# 1-Schematic_No_filter_booth_pcb.net
KiCad netlist of a schematic drawn in EasyEDA
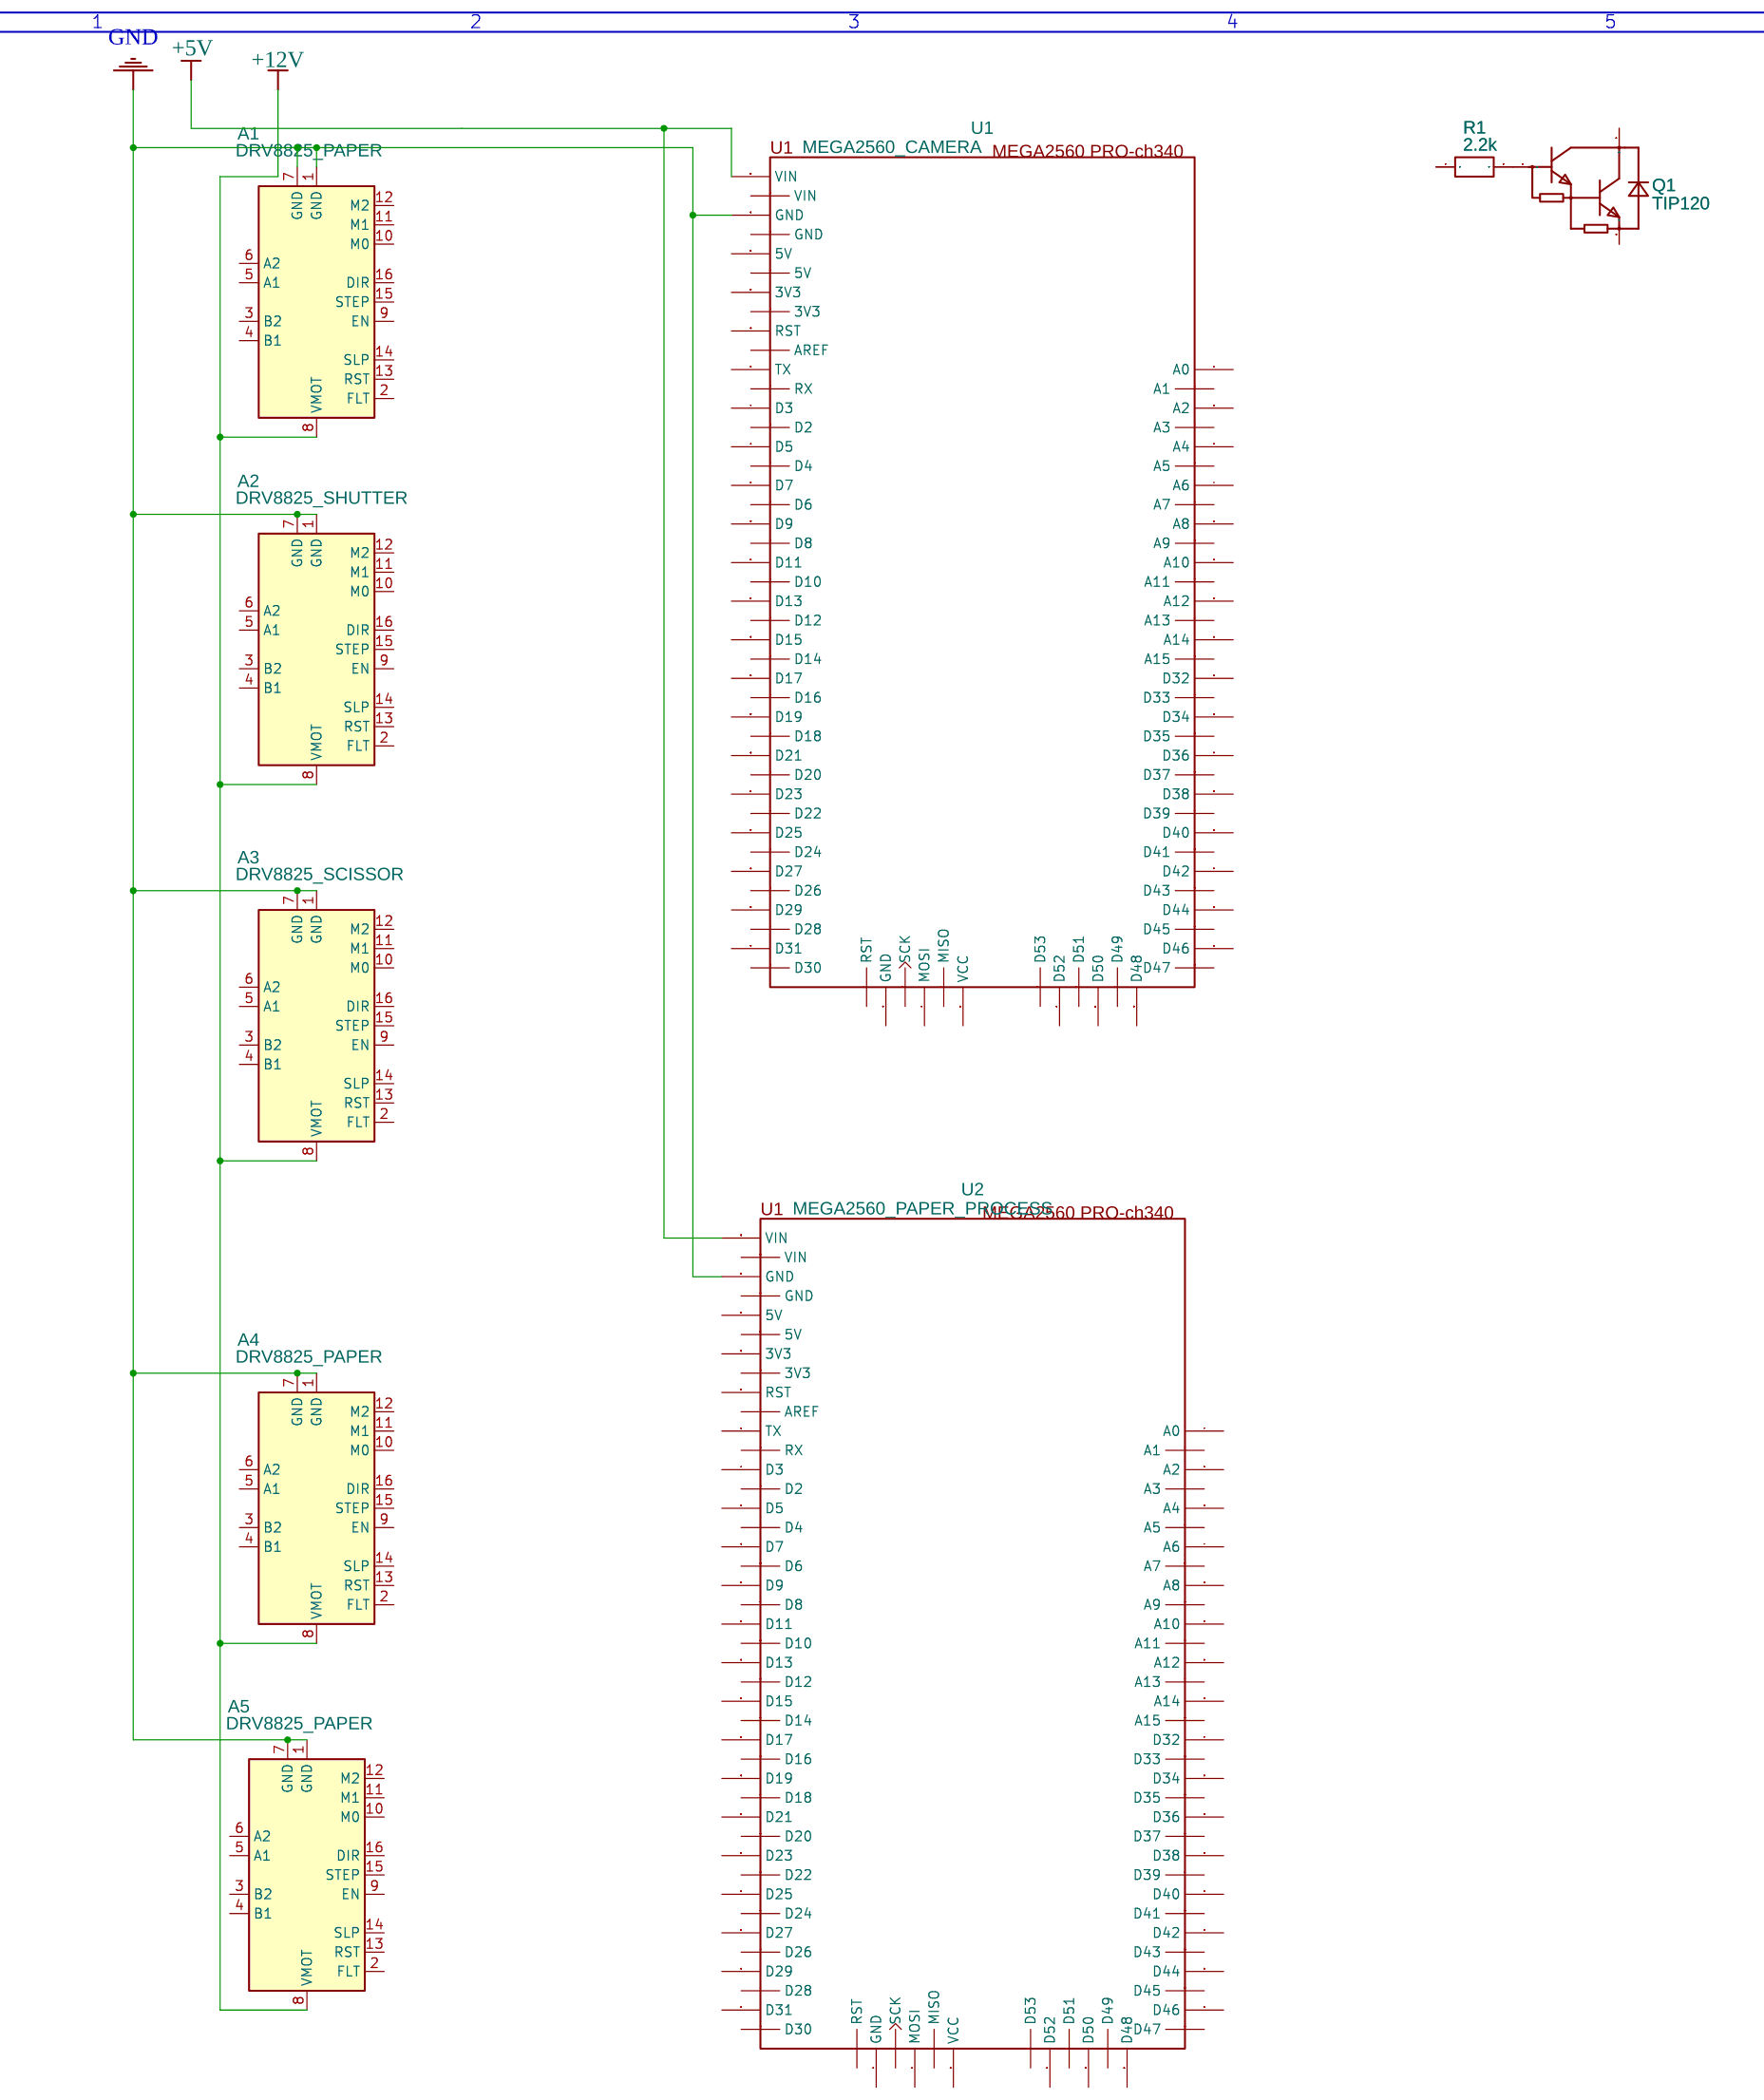
[diagram p0: schematic sheet]

(export (version "E")
  (design (tool "Eeschema 10.0.6"))
  (components
    (comp (ref "A1") (value "DRV8825_PAPER") (libsource (lib "") (part "Pololu_Breakout_DRV8825")))
    (comp (ref "A2") (value "DRV8825_SHUTTER") (libsource (lib "") (part "Pololu_Breakout_DRV8825")))
    (comp (ref "A3") (value "DRV8825_SCISSOR") (libsource (lib "") (part "Pololu_Breakout_DRV8825")))
    (comp (ref "A4") (value "DRV8825_PAPER") (libsource (lib "") (part "Pololu_Breakout_DRV8825")))
    (comp (ref "A5") (value "DRV8825_PAPER") (libsource (lib "") (part "Pololu_Breakout_DRV8825")))
    (comp (ref "Q1")
      (value "TIP120")
      (fields (field (name "BOM_Supplier Part") "C262990"))
      (libsource (lib "") (part "TIP120"))
    )
    (comp (ref "R1") (value "2.2k") (libsource (lib "") (part "Res_1210(1/3W)_EU")))
    (comp (ref "U1")
      (value "MEGA2560_CAMERA")
      (fields (field (name "BOM_Manufacturer Part") "MEGA2560 PRO-ch340G"))
      (libsource (lib "") (part "MEGA2560 PRO-ch340G"))
    )
    (comp (ref "U2")
      (value "MEGA2560_PAPER_PROCESS")
      (fields (field (name "BOM_Manufacturer Part") "MEGA2560 PRO-ch340G"))
      (libsource (lib "") (part "MEGA2560 PRO-ch340G"))
    )
  )
  (nets
    (net (code "1") (name "+5V") (class "Default")
      (node (ref "U1") (pin "86") (pinfunction "VIN_86") (pintype "unspecified"))
      (node (ref "U2") (pin "86") (pinfunction "VIN_86") (pintype "unspecified"))
    )
    (net (code "2") (name "+12V") (class "Default")
      (node (ref "A1") (pin "8") (pinfunction "VMOT_8") (pintype "bidirectional"))
      (node (ref "A2") (pin "8") (pinfunction "VMOT_8") (pintype "bidirectional"))
      (node (ref "A3") (pin "8") (pinfunction "VMOT_8") (pintype "bidirectional"))
      (node (ref "A4") (pin "8") (pinfunction "VMOT_8") (pintype "bidirectional"))
      (node (ref "A5") (pin "8") (pinfunction "VMOT_8") (pintype "bidirectional"))
    )
    (net (code "3") (name "GND") (class "Default")
      (node (ref "A1") (pin "1") (pinfunction "GND_1") (pintype "bidirectional"))
      (node (ref "A1") (pin "7") (pinfunction "GND_7") (pintype "bidirectional"))
      (node (ref "A2") (pin "1") (pinfunction "GND_1") (pintype "bidirectional"))
      (node (ref "A2") (pin "7") (pinfunction "GND_7") (pintype "bidirectional"))
      (node (ref "A3") (pin "1") (pinfunction "GND_1") (pintype "bidirectional"))
      (node (ref "A3") (pin "7") (pinfunction "GND_7") (pintype "bidirectional"))
      (node (ref "A4") (pin "1") (pinfunction "GND_1") (pintype "bidirectional"))
      (node (ref "A4") (pin "7") (pinfunction "GND_7") (pintype "bidirectional"))
      (node (ref "A5") (pin "1") (pinfunction "GND_1") (pintype "bidirectional"))
      (node (ref "A5") (pin "7") (pinfunction "GND_7") (pintype "bidirectional"))
      (node (ref "U1") (pin "84") (pinfunction "GND_84") (pintype "unspecified"))
      (node (ref "U2") (pin "84") (pinfunction "GND_84") (pintype "unspecified"))
    )
    (net (code "4") (name "Net-(Q1-B)") (class "Default")
      (node (ref "Q1") (pin "1") (pinfunction "B_1") (pintype "input"))
      (node (ref "R1") (pin "2") (pinfunction "2_2") (pintype "unspecified"))
    )
    (net (code "5") (name "unconnected-(A1-A1-Pad5)") (class "Default")
      (node (ref "A1") (pin "5") (pinfunction "A1_5") (pintype "output"))
    )
    (net (code "6") (name "unconnected-(A1-A2-Pad6)") (class "Default")
      (node (ref "A1") (pin "6") (pinfunction "A2_6") (pintype "output"))
    )
    (net (code "7") (name "unconnected-(A1-B1-Pad4)") (class "Default")
      (node (ref "A1") (pin "4") (pinfunction "B1_4") (pintype "output"))
    )
    (net (code "8") (name "unconnected-(A1-B2-Pad3)") (class "Default")
      (node (ref "A1") (pin "3") (pinfunction "B2_3") (pintype "output"))
    )
    (net (code "9") (name "unconnected-(A1-DIR-Pad16)") (class "Default")
      (node (ref "A1") (pin "16") (pinfunction "DIR_16") (pintype "input"))
    )
    (net (code "10") (name "unconnected-(A1-EN-Pad9)") (class "Default")
      (node (ref "A1") (pin "9") (pinfunction "EN_9") (pintype "input"))
    )
    (net (code "11") (name "unconnected-(A1-FLT-Pad2)") (class "Default")
      (node (ref "A1") (pin "2") (pinfunction "FLT_2") (pintype "output"))
    )
    (net (code "12") (name "unconnected-(A1-M0-Pad10)") (class "Default")
      (node (ref "A1") (pin "10") (pinfunction "M0_10") (pintype "input"))
    )
    (net (code "13") (name "unconnected-(A1-M1-Pad11)") (class "Default")
      (node (ref "A1") (pin "11") (pinfunction "M1_11") (pintype "input"))
    )
    (net (code "14") (name "unconnected-(A1-M2-Pad12)") (class "Default")
      (node (ref "A1") (pin "12") (pinfunction "M2_12") (pintype "input"))
    )
    (net (code "15") (name "unconnected-(A1-RST-Pad13)") (class "Default")
      (node (ref "A1") (pin "13") (pinfunction "RST_13") (pintype "input"))
    )
    (net (code "16") (name "unconnected-(A1-SLP-Pad14)") (class "Default")
      (node (ref "A1") (pin "14") (pinfunction "SLP_14") (pintype "input"))
    )
    (net (code "17") (name "unconnected-(A1-STEP-Pad15)") (class "Default")
      (node (ref "A1") (pin "15") (pinfunction "STEP_15") (pintype "input"))
    )
    (net (code "18") (name "unconnected-(A2-A1-Pad5)") (class "Default")
      (node (ref "A2") (pin "5") (pinfunction "A1_5") (pintype "output"))
    )
    (net (code "19") (name "unconnected-(A2-A2-Pad6)") (class "Default")
      (node (ref "A2") (pin "6") (pinfunction "A2_6") (pintype "output"))
    )
    (net (code "20") (name "unconnected-(A2-B1-Pad4)") (class "Default")
      (node (ref "A2") (pin "4") (pinfunction "B1_4") (pintype "output"))
    )
    (net (code "21") (name "unconnected-(A2-B2-Pad3)") (class "Default")
      (node (ref "A2") (pin "3") (pinfunction "B2_3") (pintype "output"))
    )
    (net (code "22") (name "unconnected-(A2-DIR-Pad16)") (class "Default")
      (node (ref "A2") (pin "16") (pinfunction "DIR_16") (pintype "input"))
    )
    (net (code "23") (name "unconnected-(A2-EN-Pad9)") (class "Default")
      (node (ref "A2") (pin "9") (pinfunction "EN_9") (pintype "input"))
    )
    (net (code "24") (name "unconnected-(A2-FLT-Pad2)") (class "Default")
      (node (ref "A2") (pin "2") (pinfunction "FLT_2") (pintype "output"))
    )
    (net (code "25") (name "unconnected-(A2-M0-Pad10)") (class "Default")
      (node (ref "A2") (pin "10") (pinfunction "M0_10") (pintype "input"))
    )
    (net (code "26") (name "unconnected-(A2-M1-Pad11)") (class "Default")
      (node (ref "A2") (pin "11") (pinfunction "M1_11") (pintype "input"))
    )
    (net (code "27") (name "unconnected-(A2-M2-Pad12)") (class "Default")
      (node (ref "A2") (pin "12") (pinfunction "M2_12") (pintype "input"))
    )
    (net (code "28") (name "unconnected-(A2-RST-Pad13)") (class "Default")
      (node (ref "A2") (pin "13") (pinfunction "RST_13") (pintype "input"))
    )
    (net (code "29") (name "unconnected-(A2-SLP-Pad14)") (class "Default")
      (node (ref "A2") (pin "14") (pinfunction "SLP_14") (pintype "input"))
    )
    (net (code "30") (name "unconnected-(A2-STEP-Pad15)") (class "Default")
      (node (ref "A2") (pin "15") (pinfunction "STEP_15") (pintype "input"))
    )
    (net (code "31") (name "unconnected-(A3-A1-Pad5)") (class "Default")
      (node (ref "A3") (pin "5") (pinfunction "A1_5") (pintype "output"))
    )
    (net (code "32") (name "unconnected-(A3-A2-Pad6)") (class "Default")
      (node (ref "A3") (pin "6") (pinfunction "A2_6") (pintype "output"))
    )
    (net (code "33") (name "unconnected-(A3-B1-Pad4)") (class "Default")
      (node (ref "A3") (pin "4") (pinfunction "B1_4") (pintype "output"))
    )
    (net (code "34") (name "unconnected-(A3-B2-Pad3)") (class "Default")
      (node (ref "A3") (pin "3") (pinfunction "B2_3") (pintype "output"))
    )
    (net (code "35") (name "unconnected-(A3-DIR-Pad16)") (class "Default")
      (node (ref "A3") (pin "16") (pinfunction "DIR_16") (pintype "input"))
    )
    (net (code "36") (name "unconnected-(A3-EN-Pad9)") (class "Default")
      (node (ref "A3") (pin "9") (pinfunction "EN_9") (pintype "input"))
    )
    (net (code "37") (name "unconnected-(A3-FLT-Pad2)") (class "Default")
      (node (ref "A3") (pin "2") (pinfunction "FLT_2") (pintype "output"))
    )
    (net (code "38") (name "unconnected-(A3-M0-Pad10)") (class "Default")
      (node (ref "A3") (pin "10") (pinfunction "M0_10") (pintype "input"))
    )
    (net (code "39") (name "unconnected-(A3-M1-Pad11)") (class "Default")
      (node (ref "A3") (pin "11") (pinfunction "M1_11") (pintype "input"))
    )
    (net (code "40") (name "unconnected-(A3-M2-Pad12)") (class "Default")
      (node (ref "A3") (pin "12") (pinfunction "M2_12") (pintype "input"))
    )
    (net (code "41") (name "unconnected-(A3-RST-Pad13)") (class "Default")
      (node (ref "A3") (pin "13") (pinfunction "RST_13") (pintype "input"))
    )
    (net (code "42") (name "unconnected-(A3-SLP-Pad14)") (class "Default")
      (node (ref "A3") (pin "14") (pinfunction "SLP_14") (pintype "input"))
    )
    (net (code "43") (name "unconnected-(A3-STEP-Pad15)") (class "Default")
      (node (ref "A3") (pin "15") (pinfunction "STEP_15") (pintype "input"))
    )
    (net (code "44") (name "unconnected-(A4-A1-Pad5)") (class "Default")
      (node (ref "A4") (pin "5") (pinfunction "A1_5") (pintype "output"))
    )
    (net (code "45") (name "unconnected-(A4-A2-Pad6)") (class "Default")
      (node (ref "A4") (pin "6") (pinfunction "A2_6") (pintype "output"))
    )
    (net (code "46") (name "unconnected-(A4-B1-Pad4)") (class "Default")
      (node (ref "A4") (pin "4") (pinfunction "B1_4") (pintype "output"))
    )
    (net (code "47") (name "unconnected-(A4-B2-Pad3)") (class "Default")
      (node (ref "A4") (pin "3") (pinfunction "B2_3") (pintype "output"))
    )
    (net (code "48") (name "unconnected-(A4-DIR-Pad16)") (class "Default")
      (node (ref "A4") (pin "16") (pinfunction "DIR_16") (pintype "input"))
    )
    (net (code "49") (name "unconnected-(A4-EN-Pad9)") (class "Default")
      (node (ref "A4") (pin "9") (pinfunction "EN_9") (pintype "input"))
    )
    (net (code "50") (name "unconnected-(A4-FLT-Pad2)") (class "Default")
      (node (ref "A4") (pin "2") (pinfunction "FLT_2") (pintype "output"))
    )
    (net (code "51") (name "unconnected-(A4-M0-Pad10)") (class "Default")
      (node (ref "A4") (pin "10") (pinfunction "M0_10") (pintype "input"))
    )
    (net (code "52") (name "unconnected-(A4-M1-Pad11)") (class "Default")
      (node (ref "A4") (pin "11") (pinfunction "M1_11") (pintype "input"))
    )
    (net (code "53") (name "unconnected-(A4-M2-Pad12)") (class "Default")
      (node (ref "A4") (pin "12") (pinfunction "M2_12") (pintype "input"))
    )
    (net (code "54") (name "unconnected-(A4-RST-Pad13)") (class "Default")
      (node (ref "A4") (pin "13") (pinfunction "RST_13") (pintype "input"))
    )
    (net (code "55") (name "unconnected-(A4-SLP-Pad14)") (class "Default")
      (node (ref "A4") (pin "14") (pinfunction "SLP_14") (pintype "input"))
    )
    (net (code "56") (name "unconnected-(A4-STEP-Pad15)") (class "Default")
      (node (ref "A4") (pin "15") (pinfunction "STEP_15") (pintype "input"))
    )
    (net (code "57") (name "unconnected-(A5-A1-Pad5)") (class "Default")
      (node (ref "A5") (pin "5") (pinfunction "A1_5") (pintype "output"))
    )
    (net (code "58") (name "unconnected-(A5-A2-Pad6)") (class "Default")
      (node (ref "A5") (pin "6") (pinfunction "A2_6") (pintype "output"))
    )
    (net (code "59") (name "unconnected-(A5-B1-Pad4)") (class "Default")
      (node (ref "A5") (pin "4") (pinfunction "B1_4") (pintype "output"))
    )
    (net (code "60") (name "unconnected-(A5-B2-Pad3)") (class "Default")
      (node (ref "A5") (pin "3") (pinfunction "B2_3") (pintype "output"))
    )
    (net (code "61") (name "unconnected-(A5-DIR-Pad16)") (class "Default")
      (node (ref "A5") (pin "16") (pinfunction "DIR_16") (pintype "input"))
    )
    (net (code "62") (name "unconnected-(A5-EN-Pad9)") (class "Default")
      (node (ref "A5") (pin "9") (pinfunction "EN_9") (pintype "input"))
    )
    (net (code "63") (name "unconnected-(A5-FLT-Pad2)") (class "Default")
      (node (ref "A5") (pin "2") (pinfunction "FLT_2") (pintype "output"))
    )
    (net (code "64") (name "unconnected-(A5-M0-Pad10)") (class "Default")
      (node (ref "A5") (pin "10") (pinfunction "M0_10") (pintype "input"))
    )
    (net (code "65") (name "unconnected-(A5-M1-Pad11)") (class "Default")
      (node (ref "A5") (pin "11") (pinfunction "M1_11") (pintype "input"))
    )
    (net (code "66") (name "unconnected-(A5-M2-Pad12)") (class "Default")
      (node (ref "A5") (pin "12") (pinfunction "M2_12") (pintype "input"))
    )
    (net (code "67") (name "unconnected-(A5-RST-Pad13)") (class "Default")
      (node (ref "A5") (pin "13") (pinfunction "RST_13") (pintype "input"))
    )
    (net (code "68") (name "unconnected-(A5-SLP-Pad14)") (class "Default")
      (node (ref "A5") (pin "14") (pinfunction "SLP_14") (pintype "input"))
    )
    (net (code "69") (name "unconnected-(A5-STEP-Pad15)") (class "Default")
      (node (ref "A5") (pin "15") (pinfunction "STEP_15") (pintype "input"))
    )
    (net (code "70") (name "unconnected-(Q1-C-Pad2)") (class "Default")
      (node (ref "Q1") (pin "2") (pinfunction "C_2") (pintype "input"))
    )
    (net (code "71") (name "unconnected-(Q1-E-Pad3)") (class "Default")
      (node (ref "Q1") (pin "3") (pinfunction "E_3") (pintype "input"))
    )
    (net (code "72") (name "unconnected-(R1-Pad1)") (class "Default")
      (node (ref "R1") (pin "1") (pinfunction "1_1") (pintype "unspecified"))
    )
    (net (code "73") (name "unconnected-(U1-3V3-Pad79)") (class "Default")
      (node (ref "U1") (pin "79") (pinfunction "3V3_79") (pintype "unspecified"))
    )
    (net (code "74") (name "unconnected-(U1-3V3-Pad80)") (class "Default")
      (node (ref "U1") (pin "80") (pinfunction "3V3_80") (pintype "unspecified"))
    )
    (net (code "75") (name "unconnected-(U1-5V-Pad81)") (class "Default")
      (node (ref "U1") (pin "81") (pinfunction "5V_81") (pintype "unspecified"))
    )
    (net (code "76") (name "unconnected-(U1-5V-Pad82)") (class "Default")
      (node (ref "U1") (pin "82") (pinfunction "5V_82") (pintype "unspecified"))
    )
    (net (code "77") (name "unconnected-(U1-A0-Pad1)") (class "Default")
      (node (ref "U1") (pin "1") (pinfunction "A0_1") (pintype "unspecified"))
    )
    (net (code "78") (name "unconnected-(U1-A1-Pad2)") (class "Default")
      (node (ref "U1") (pin "2") (pinfunction "A1_2") (pintype "unspecified"))
    )
    (net (code "79") (name "unconnected-(U1-A2-Pad3)") (class "Default")
      (node (ref "U1") (pin "3") (pinfunction "A2_3") (pintype "unspecified"))
    )
    (net (code "80") (name "unconnected-(U1-A3-Pad4)") (class "Default")
      (node (ref "U1") (pin "4") (pinfunction "A3_4") (pintype "unspecified"))
    )
    (net (code "81") (name "unconnected-(U1-A4-Pad5)") (class "Default")
      (node (ref "U1") (pin "5") (pinfunction "A4_5") (pintype "unspecified"))
    )
    (net (code "82") (name "unconnected-(U1-A5-Pad6)") (class "Default")
      (node (ref "U1") (pin "6") (pinfunction "A5_6") (pintype "unspecified"))
    )
    (net (code "83") (name "unconnected-(U1-A6-Pad7)") (class "Default")
      (node (ref "U1") (pin "7") (pinfunction "A6_7") (pintype "unspecified"))
    )
    (net (code "84") (name "unconnected-(U1-A7-Pad8)") (class "Default")
      (node (ref "U1") (pin "8") (pinfunction "A7_8") (pintype "unspecified"))
    )
    (net (code "85") (name "unconnected-(U1-A8-Pad9)") (class "Default")
      (node (ref "U1") (pin "9") (pinfunction "A8_9") (pintype "unspecified"))
    )
    (net (code "86") (name "unconnected-(U1-A9-Pad10)") (class "Default")
      (node (ref "U1") (pin "10") (pinfunction "A9_10") (pintype "unspecified"))
    )
    (net (code "87") (name "unconnected-(U1-A10-Pad11)") (class "Default")
      (node (ref "U1") (pin "11") (pinfunction "A10_11") (pintype "unspecified"))
    )
    (net (code "88") (name "unconnected-(U1-A11-Pad12)") (class "Default")
      (node (ref "U1") (pin "12") (pinfunction "A11_12") (pintype "unspecified"))
    )
    (net (code "89") (name "unconnected-(U1-A12-Pad13)") (class "Default")
      (node (ref "U1") (pin "13") (pinfunction "A12_13") (pintype "unspecified"))
    )
    (net (code "90") (name "unconnected-(U1-A13-Pad14)") (class "Default")
      (node (ref "U1") (pin "14") (pinfunction "A13_14") (pintype "unspecified"))
    )
    (net (code "91") (name "unconnected-(U1-A14-Pad15)") (class "Default")
      (node (ref "U1") (pin "15") (pinfunction "A14_15") (pintype "unspecified"))
    )
    (net (code "92") (name "unconnected-(U1-A15-Pad16)") (class "Default")
      (node (ref "U1") (pin "16") (pinfunction "A15_16") (pintype "unspecified"))
    )
    (net (code "93") (name "unconnected-(U1-AREF-Pad77)") (class "Default")
      (node (ref "U1") (pin "77") (pinfunction "AREF_77") (pintype "unspecified"))
    )
    (net (code "94") (name "unconnected-(U1-D2-Pad73)") (class "Default")
      (node (ref "U1") (pin "73") (pinfunction "D2_73") (pintype "unspecified"))
    )
    (net (code "95") (name "unconnected-(U1-D3-Pad74)") (class "Default")
      (node (ref "U1") (pin "74") (pinfunction "D3_74") (pintype "unspecified"))
    )
    (net (code "96") (name "unconnected-(U1-D4-Pad71)") (class "Default")
      (node (ref "U1") (pin "71") (pinfunction "D4_71") (pintype "unspecified"))
    )
    (net (code "97") (name "unconnected-(U1-D5-Pad72)") (class "Default")
      (node (ref "U1") (pin "72") (pinfunction "D5_72") (pintype "unspecified"))
    )
    (net (code "98") (name "unconnected-(U1-D6-Pad69)") (class "Default")
      (node (ref "U1") (pin "69") (pinfunction "D6_69") (pintype "unspecified"))
    )
    (net (code "99") (name "unconnected-(U1-D7-Pad70)") (class "Default")
      (node (ref "U1") (pin "70") (pinfunction "D7_70") (pintype "unspecified"))
    )
    (net (code "100") (name "unconnected-(U1-D8-Pad67)") (class "Default")
      (node (ref "U1") (pin "67") (pinfunction "D8_67") (pintype "unspecified"))
    )
    (net (code "101") (name "unconnected-(U1-D9-Pad68)") (class "Default")
      (node (ref "U1") (pin "68") (pinfunction "D9_68") (pintype "unspecified"))
    )
    (net (code "102") (name "unconnected-(U1-D10-Pad65)") (class "Default")
      (node (ref "U1") (pin "65") (pinfunction "D10_65") (pintype "unspecified"))
    )
    (net (code "103") (name "unconnected-(U1-D11-Pad66)") (class "Default")
      (node (ref "U1") (pin "66") (pinfunction "D11_66") (pintype "bidirectional"))
    )
    (net (code "104") (name "unconnected-(U1-D12-Pad63)") (class "Default")
      (node (ref "U1") (pin "63") (pinfunction "D12_63") (pintype "unspecified"))
    )
    (net (code "105") (name "unconnected-(U1-D13-Pad64)") (class "Default")
      (node (ref "U1") (pin "64") (pinfunction "D13_64") (pintype "unspecified"))
    )
    (net (code "106") (name "unconnected-(U1-D14-Pad61)") (class "Default")
      (node (ref "U1") (pin "61") (pinfunction "D14_61") (pintype "unspecified"))
    )
    (net (code "107") (name "unconnected-(U1-D15-Pad62)") (class "Default")
      (node (ref "U1") (pin "62") (pinfunction "D15_62") (pintype "unspecified"))
    )
    (net (code "108") (name "unconnected-(U1-D16-Pad59)") (class "Default")
      (node (ref "U1") (pin "59") (pinfunction "D16_59") (pintype "unspecified"))
    )
    (net (code "109") (name "unconnected-(U1-D17-Pad60)") (class "Default")
      (node (ref "U1") (pin "60") (pinfunction "D17_60") (pintype "unspecified"))
    )
    (net (code "110") (name "unconnected-(U1-D18-Pad57)") (class "Default")
      (node (ref "U1") (pin "57") (pinfunction "D18_57") (pintype "unspecified"))
    )
    (net (code "111") (name "unconnected-(U1-D19-Pad58)") (class "Default")
      (node (ref "U1") (pin "58") (pinfunction "D19_58") (pintype "unspecified"))
    )
    (net (code "112") (name "unconnected-(U1-D20-Pad55)") (class "Default")
      (node (ref "U1") (pin "55") (pinfunction "D20_55") (pintype "unspecified"))
    )
    (net (code "113") (name "unconnected-(U1-D21-Pad56)") (class "Default")
      (node (ref "U1") (pin "56") (pinfunction "D21_56") (pintype "unspecified"))
    )
    (net (code "114") (name "unconnected-(U1-D22-Pad53)") (class "Default")
      (node (ref "U1") (pin "53") (pinfunction "D22_53") (pintype "unspecified"))
    )
    (net (code "115") (name "unconnected-(U1-D23-Pad54)") (class "Default")
      (node (ref "U1") (pin "54") (pinfunction "D23_54") (pintype "unspecified"))
    )
    (net (code "116") (name "unconnected-(U1-D24-Pad51)") (class "Default")
      (node (ref "U1") (pin "51") (pinfunction "D24_51") (pintype "unspecified"))
    )
    (net (code "117") (name "unconnected-(U1-D25-Pad52)") (class "Default")
      (node (ref "U1") (pin "52") (pinfunction "D25_52") (pintype "unspecified"))
    )
    (net (code "118") (name "unconnected-(U1-D26-Pad49)") (class "Default")
      (node (ref "U1") (pin "49") (pinfunction "D26_49") (pintype "unspecified"))
    )
    (net (code "119") (name "unconnected-(U1-D27-Pad50)") (class "Default")
      (node (ref "U1") (pin "50") (pinfunction "D27_50") (pintype "unspecified"))
    )
    (net (code "120") (name "unconnected-(U1-D28-Pad47)") (class "Default")
      (node (ref "U1") (pin "47") (pinfunction "D28_47") (pintype "unspecified"))
    )
    (net (code "121") (name "unconnected-(U1-D29-Pad48)") (class "Default")
      (node (ref "U1") (pin "48") (pinfunction "D29_48") (pintype "unspecified"))
    )
    (net (code "122") (name "unconnected-(U1-D30-Pad45)") (class "Default")
      (node (ref "U1") (pin "45") (pinfunction "D30_45") (pintype "unspecified"))
    )
    (net (code "123") (name "unconnected-(U1-D31-Pad46)") (class "Default")
      (node (ref "U1") (pin "46") (pinfunction "D31_46") (pintype "unspecified"))
    )
    (net (code "124") (name "unconnected-(U1-D32-Pad17)") (class "Default")
      (node (ref "U1") (pin "17") (pinfunction "D32_17") (pintype "unspecified"))
    )
    (net (code "125") (name "unconnected-(U1-D33-Pad18)") (class "Default")
      (node (ref "U1") (pin "18") (pinfunction "D33_18") (pintype "unspecified"))
    )
    (net (code "126") (name "unconnected-(U1-D34-Pad19)") (class "Default")
      (node (ref "U1") (pin "19") (pinfunction "D34_19") (pintype "unspecified"))
    )
    (net (code "127") (name "unconnected-(U1-D35-Pad20)") (class "Default")
      (node (ref "U1") (pin "20") (pinfunction "D35_20") (pintype "unspecified"))
    )
    (net (code "128") (name "unconnected-(U1-D36-Pad21)") (class "Default")
      (node (ref "U1") (pin "21") (pinfunction "D36_21") (pintype "unspecified"))
    )
    (net (code "129") (name "unconnected-(U1-D37-Pad22)") (class "Default")
      (node (ref "U1") (pin "22") (pinfunction "D37_22") (pintype "unspecified"))
    )
    (net (code "130") (name "unconnected-(U1-D38-Pad23)") (class "Default")
      (node (ref "U1") (pin "23") (pinfunction "D38_23") (pintype "unspecified"))
    )
    (net (code "131") (name "unconnected-(U1-D39-Pad24)") (class "Default")
      (node (ref "U1") (pin "24") (pinfunction "D39_24") (pintype "unspecified"))
    )
    (net (code "132") (name "unconnected-(U1-D40-Pad25)") (class "Default")
      (node (ref "U1") (pin "25") (pinfunction "D40_25") (pintype "unspecified"))
    )
    (net (code "133") (name "unconnected-(U1-D41-Pad26)") (class "Default")
      (node (ref "U1") (pin "26") (pinfunction "D41_26") (pintype "unspecified"))
    )
    (net (code "134") (name "unconnected-(U1-D42-Pad27)") (class "Default")
      (node (ref "U1") (pin "27") (pinfunction "D42_27") (pintype "unspecified"))
    )
    (net (code "135") (name "unconnected-(U1-D43-Pad28)") (class "Default")
      (node (ref "U1") (pin "28") (pinfunction "D43_28") (pintype "unspecified"))
    )
    (net (code "136") (name "unconnected-(U1-D44-Pad29)") (class "Default")
      (node (ref "U1") (pin "29") (pinfunction "D44_29") (pintype "unspecified"))
    )
    (net (code "137") (name "unconnected-(U1-D45-Pad30)") (class "Default")
      (node (ref "U1") (pin "30") (pinfunction "D45_30") (pintype "unspecified"))
    )
    (net (code "138") (name "unconnected-(U1-D46-Pad31)") (class "Default")
      (node (ref "U1") (pin "31") (pinfunction "D46_31") (pintype "unspecified"))
    )
    (net (code "139") (name "unconnected-(U1-D47-Pad32)") (class "Default")
      (node (ref "U1") (pin "32") (pinfunction "D47_32") (pintype "unspecified"))
    )
    (net (code "140") (name "unconnected-(U1-D48-Pad33)") (class "Default")
      (node (ref "U1") (pin "33") (pinfunction "D48_33") (pintype "unspecified"))
    )
    (net (code "141") (name "unconnected-(U1-D49-Pad34)") (class "Default")
      (node (ref "U1") (pin "34") (pinfunction "D49_34") (pintype "unspecified"))
    )
    (net (code "142") (name "unconnected-(U1-D50-Pad35)") (class "Default")
      (node (ref "U1") (pin "35") (pinfunction "D50_35") (pintype "unspecified"))
    )
    (net (code "143") (name "unconnected-(U1-D51-Pad36)") (class "Default")
      (node (ref "U1") (pin "36") (pinfunction "D51_36") (pintype "unspecified"))
    )
    (net (code "144") (name "unconnected-(U1-D52-Pad37)") (class "Default")
      (node (ref "U1") (pin "37") (pinfunction "D52_37") (pintype "unspecified"))
    )
    (net (code "145") (name "unconnected-(U1-D53-Pad38)") (class "Default")
      (node (ref "U1") (pin "38") (pinfunction "D53_38") (pintype "unspecified"))
    )
    (net (code "146") (name "unconnected-(U1-GND-Pad43)") (class "Default")
      (node (ref "U1") (pin "43") (pinfunction "GND_43") (pintype "unspecified"))
    )
    (net (code "147") (name "unconnected-(U1-GND-Pad83)") (class "Default")
      (node (ref "U1") (pin "83") (pinfunction "GND_83") (pintype "unspecified"))
    )
    (net (code "148") (name "unconnected-(U1-MISO-Pad40)") (class "Default")
      (node (ref "U1") (pin "40") (pinfunction "MISO_40") (pintype "unspecified"))
    )
    (net (code "149") (name "unconnected-(U1-MOSI-Pad41)") (class "Default")
      (node (ref "U1") (pin "41") (pinfunction "MOSI_41") (pintype "unspecified"))
    )
    (net (code "150") (name "unconnected-(U1-RST-Pad44)") (class "Default")
      (node (ref "U1") (pin "44") (pinfunction "RST_44") (pintype "unspecified"))
    )
    (net (code "151") (name "unconnected-(U1-RST-Pad78)") (class "Default")
      (node (ref "U1") (pin "78") (pinfunction "RST_78") (pintype "unspecified"))
    )
    (net (code "152") (name "unconnected-(U1-RX-Pad75)") (class "Default")
      (node (ref "U1") (pin "75") (pinfunction "RX_75") (pintype "unspecified"))
    )
    (net (code "153") (name "unconnected-(U1-SCK-Pad42)") (class "Default")
      (node (ref "U1") (pin "42") (pinfunction "SCK_42") (pintype "unspecified"))
    )
    (net (code "154") (name "unconnected-(U1-TX-Pad76)") (class "Default")
      (node (ref "U1") (pin "76") (pinfunction "TX_76") (pintype "unspecified"))
    )
    (net (code "155") (name "unconnected-(U1-VCC-Pad39)") (class "Default")
      (node (ref "U1") (pin "39") (pinfunction "VCC_39") (pintype "unspecified"))
    )
    (net (code "156") (name "unconnected-(U1-VIN-Pad85)") (class "Default")
      (node (ref "U1") (pin "85") (pinfunction "VIN_85") (pintype "unspecified"))
    )
    (net (code "157") (name "unconnected-(U2-3V3-Pad79)") (class "Default")
      (node (ref "U2") (pin "79") (pinfunction "3V3_79") (pintype "unspecified"))
    )
    (net (code "158") (name "unconnected-(U2-3V3-Pad80)") (class "Default")
      (node (ref "U2") (pin "80") (pinfunction "3V3_80") (pintype "unspecified"))
    )
    (net (code "159") (name "unconnected-(U2-5V-Pad81)") (class "Default")
      (node (ref "U2") (pin "81") (pinfunction "5V_81") (pintype "unspecified"))
    )
    (net (code "160") (name "unconnected-(U2-5V-Pad82)") (class "Default")
      (node (ref "U2") (pin "82") (pinfunction "5V_82") (pintype "unspecified"))
    )
    (net (code "161") (name "unconnected-(U2-A0-Pad1)") (class "Default")
      (node (ref "U2") (pin "1") (pinfunction "A0_1") (pintype "unspecified"))
    )
    (net (code "162") (name "unconnected-(U2-A1-Pad2)") (class "Default")
      (node (ref "U2") (pin "2") (pinfunction "A1_2") (pintype "unspecified"))
    )
    (net (code "163") (name "unconnected-(U2-A2-Pad3)") (class "Default")
      (node (ref "U2") (pin "3") (pinfunction "A2_3") (pintype "unspecified"))
    )
    (net (code "164") (name "unconnected-(U2-A3-Pad4)") (class "Default")
      (node (ref "U2") (pin "4") (pinfunction "A3_4") (pintype "unspecified"))
    )
    (net (code "165") (name "unconnected-(U2-A4-Pad5)") (class "Default")
      (node (ref "U2") (pin "5") (pinfunction "A4_5") (pintype "unspecified"))
    )
    (net (code "166") (name "unconnected-(U2-A5-Pad6)") (class "Default")
      (node (ref "U2") (pin "6") (pinfunction "A5_6") (pintype "unspecified"))
    )
    (net (code "167") (name "unconnected-(U2-A6-Pad7)") (class "Default")
      (node (ref "U2") (pin "7") (pinfunction "A6_7") (pintype "unspecified"))
    )
    (net (code "168") (name "unconnected-(U2-A7-Pad8)") (class "Default")
      (node (ref "U2") (pin "8") (pinfunction "A7_8") (pintype "unspecified"))
    )
    (net (code "169") (name "unconnected-(U2-A8-Pad9)") (class "Default")
      (node (ref "U2") (pin "9") (pinfunction "A8_9") (pintype "unspecified"))
    )
    (net (code "170") (name "unconnected-(U2-A9-Pad10)") (class "Default")
      (node (ref "U2") (pin "10") (pinfunction "A9_10") (pintype "unspecified"))
    )
    (net (code "171") (name "unconnected-(U2-A10-Pad11)") (class "Default")
      (node (ref "U2") (pin "11") (pinfunction "A10_11") (pintype "unspecified"))
    )
    (net (code "172") (name "unconnected-(U2-A11-Pad12)") (class "Default")
      (node (ref "U2") (pin "12") (pinfunction "A11_12") (pintype "unspecified"))
    )
    (net (code "173") (name "unconnected-(U2-A12-Pad13)") (class "Default")
      (node (ref "U2") (pin "13") (pinfunction "A12_13") (pintype "unspecified"))
    )
    (net (code "174") (name "unconnected-(U2-A13-Pad14)") (class "Default")
      (node (ref "U2") (pin "14") (pinfunction "A13_14") (pintype "unspecified"))
    )
    (net (code "175") (name "unconnected-(U2-A14-Pad15)") (class "Default")
      (node (ref "U2") (pin "15") (pinfunction "A14_15") (pintype "unspecified"))
    )
    (net (code "176") (name "unconnected-(U2-A15-Pad16)") (class "Default")
      (node (ref "U2") (pin "16") (pinfunction "A15_16") (pintype "unspecified"))
    )
    (net (code "177") (name "unconnected-(U2-AREF-Pad77)") (class "Default")
      (node (ref "U2") (pin "77") (pinfunction "AREF_77") (pintype "unspecified"))
    )
    (net (code "178") (name "unconnected-(U2-D2-Pad73)") (class "Default")
      (node (ref "U2") (pin "73") (pinfunction "D2_73") (pintype "unspecified"))
    )
    (net (code "179") (name "unconnected-(U2-D3-Pad74)") (class "Default")
      (node (ref "U2") (pin "74") (pinfunction "D3_74") (pintype "unspecified"))
    )
    (net (code "180") (name "unconnected-(U2-D4-Pad71)") (class "Default")
      (node (ref "U2") (pin "71") (pinfunction "D4_71") (pintype "unspecified"))
    )
    (net (code "181") (name "unconnected-(U2-D5-Pad72)") (class "Default")
      (node (ref "U2") (pin "72") (pinfunction "D5_72") (pintype "unspecified"))
    )
    (net (code "182") (name "unconnected-(U2-D6-Pad69)") (class "Default")
      (node (ref "U2") (pin "69") (pinfunction "D6_69") (pintype "unspecified"))
    )
    (net (code "183") (name "unconnected-(U2-D7-Pad70)") (class "Default")
      (node (ref "U2") (pin "70") (pinfunction "D7_70") (pintype "unspecified"))
    )
    (net (code "184") (name "unconnected-(U2-D8-Pad67)") (class "Default")
      (node (ref "U2") (pin "67") (pinfunction "D8_67") (pintype "unspecified"))
    )
    (net (code "185") (name "unconnected-(U2-D9-Pad68)") (class "Default")
      (node (ref "U2") (pin "68") (pinfunction "D9_68") (pintype "unspecified"))
    )
    (net (code "186") (name "unconnected-(U2-D10-Pad65)") (class "Default")
      (node (ref "U2") (pin "65") (pinfunction "D10_65") (pintype "unspecified"))
    )
    (net (code "187") (name "unconnected-(U2-D11-Pad66)") (class "Default")
      (node (ref "U2") (pin "66") (pinfunction "D11_66") (pintype "bidirectional"))
    )
    (net (code "188") (name "unconnected-(U2-D12-Pad63)") (class "Default")
      (node (ref "U2") (pin "63") (pinfunction "D12_63") (pintype "unspecified"))
    )
    (net (code "189") (name "unconnected-(U2-D13-Pad64)") (class "Default")
      (node (ref "U2") (pin "64") (pinfunction "D13_64") (pintype "unspecified"))
    )
    (net (code "190") (name "unconnected-(U2-D14-Pad61)") (class "Default")
      (node (ref "U2") (pin "61") (pinfunction "D14_61") (pintype "unspecified"))
    )
    (net (code "191") (name "unconnected-(U2-D15-Pad62)") (class "Default")
      (node (ref "U2") (pin "62") (pinfunction "D15_62") (pintype "unspecified"))
    )
    (net (code "192") (name "unconnected-(U2-D16-Pad59)") (class "Default")
      (node (ref "U2") (pin "59") (pinfunction "D16_59") (pintype "unspecified"))
    )
    (net (code "193") (name "unconnected-(U2-D17-Pad60)") (class "Default")
      (node (ref "U2") (pin "60") (pinfunction "D17_60") (pintype "unspecified"))
    )
    (net (code "194") (name "unconnected-(U2-D18-Pad57)") (class "Default")
      (node (ref "U2") (pin "57") (pinfunction "D18_57") (pintype "unspecified"))
    )
    (net (code "195") (name "unconnected-(U2-D19-Pad58)") (class "Default")
      (node (ref "U2") (pin "58") (pinfunction "D19_58") (pintype "unspecified"))
    )
    (net (code "196") (name "unconnected-(U2-D20-Pad55)") (class "Default")
      (node (ref "U2") (pin "55") (pinfunction "D20_55") (pintype "unspecified"))
    )
    (net (code "197") (name "unconnected-(U2-D21-Pad56)") (class "Default")
      (node (ref "U2") (pin "56") (pinfunction "D21_56") (pintype "unspecified"))
    )
    (net (code "198") (name "unconnected-(U2-D22-Pad53)") (class "Default")
      (node (ref "U2") (pin "53") (pinfunction "D22_53") (pintype "unspecified"))
    )
    (net (code "199") (name "unconnected-(U2-D23-Pad54)") (class "Default")
      (node (ref "U2") (pin "54") (pinfunction "D23_54") (pintype "unspecified"))
    )
    (net (code "200") (name "unconnected-(U2-D24-Pad51)") (class "Default")
      (node (ref "U2") (pin "51") (pinfunction "D24_51") (pintype "unspecified"))
    )
    (net (code "201") (name "unconnected-(U2-D25-Pad52)") (class "Default")
      (node (ref "U2") (pin "52") (pinfunction "D25_52") (pintype "unspecified"))
    )
    (net (code "202") (name "unconnected-(U2-D26-Pad49)") (class "Default")
      (node (ref "U2") (pin "49") (pinfunction "D26_49") (pintype "unspecified"))
    )
    (net (code "203") (name "unconnected-(U2-D27-Pad50)") (class "Default")
      (node (ref "U2") (pin "50") (pinfunction "D27_50") (pintype "unspecified"))
    )
    (net (code "204") (name "unconnected-(U2-D28-Pad47)") (class "Default")
      (node (ref "U2") (pin "47") (pinfunction "D28_47") (pintype "unspecified"))
    )
    (net (code "205") (name "unconnected-(U2-D29-Pad48)") (class "Default")
      (node (ref "U2") (pin "48") (pinfunction "D29_48") (pintype "unspecified"))
    )
    (net (code "206") (name "unconnected-(U2-D30-Pad45)") (class "Default")
      (node (ref "U2") (pin "45") (pinfunction "D30_45") (pintype "unspecified"))
    )
    (net (code "207") (name "unconnected-(U2-D31-Pad46)") (class "Default")
      (node (ref "U2") (pin "46") (pinfunction "D31_46") (pintype "unspecified"))
    )
    (net (code "208") (name "unconnected-(U2-D32-Pad17)") (class "Default")
      (node (ref "U2") (pin "17") (pinfunction "D32_17") (pintype "unspecified"))
    )
    (net (code "209") (name "unconnected-(U2-D33-Pad18)") (class "Default")
      (node (ref "U2") (pin "18") (pinfunction "D33_18") (pintype "unspecified"))
    )
    (net (code "210") (name "unconnected-(U2-D34-Pad19)") (class "Default")
      (node (ref "U2") (pin "19") (pinfunction "D34_19") (pintype "unspecified"))
    )
    (net (code "211") (name "unconnected-(U2-D35-Pad20)") (class "Default")
      (node (ref "U2") (pin "20") (pinfunction "D35_20") (pintype "unspecified"))
    )
    (net (code "212") (name "unconnected-(U2-D36-Pad21)") (class "Default")
      (node (ref "U2") (pin "21") (pinfunction "D36_21") (pintype "unspecified"))
    )
    (net (code "213") (name "unconnected-(U2-D37-Pad22)") (class "Default")
      (node (ref "U2") (pin "22") (pinfunction "D37_22") (pintype "unspecified"))
    )
    (net (code "214") (name "unconnected-(U2-D38-Pad23)") (class "Default")
      (node (ref "U2") (pin "23") (pinfunction "D38_23") (pintype "unspecified"))
    )
    (net (code "215") (name "unconnected-(U2-D39-Pad24)") (class "Default")
      (node (ref "U2") (pin "24") (pinfunction "D39_24") (pintype "unspecified"))
    )
    (net (code "216") (name "unconnected-(U2-D40-Pad25)") (class "Default")
      (node (ref "U2") (pin "25") (pinfunction "D40_25") (pintype "unspecified"))
    )
    (net (code "217") (name "unconnected-(U2-D41-Pad26)") (class "Default")
      (node (ref "U2") (pin "26") (pinfunction "D41_26") (pintype "unspecified"))
    )
    (net (code "218") (name "unconnected-(U2-D42-Pad27)") (class "Default")
      (node (ref "U2") (pin "27") (pinfunction "D42_27") (pintype "unspecified"))
    )
    (net (code "219") (name "unconnected-(U2-D43-Pad28)") (class "Default")
      (node (ref "U2") (pin "28") (pinfunction "D43_28") (pintype "unspecified"))
    )
    (net (code "220") (name "unconnected-(U2-D44-Pad29)") (class "Default")
      (node (ref "U2") (pin "29") (pinfunction "D44_29") (pintype "unspecified"))
    )
    (net (code "221") (name "unconnected-(U2-D45-Pad30)") (class "Default")
      (node (ref "U2") (pin "30") (pinfunction "D45_30") (pintype "unspecified"))
    )
    (net (code "222") (name "unconnected-(U2-D46-Pad31)") (class "Default")
      (node (ref "U2") (pin "31") (pinfunction "D46_31") (pintype "unspecified"))
    )
    (net (code "223") (name "unconnected-(U2-D47-Pad32)") (class "Default")
      (node (ref "U2") (pin "32") (pinfunction "D47_32") (pintype "unspecified"))
    )
    (net (code "224") (name "unconnected-(U2-D48-Pad33)") (class "Default")
      (node (ref "U2") (pin "33") (pinfunction "D48_33") (pintype "unspecified"))
    )
    (net (code "225") (name "unconnected-(U2-D49-Pad34)") (class "Default")
      (node (ref "U2") (pin "34") (pinfunction "D49_34") (pintype "unspecified"))
    )
    (net (code "226") (name "unconnected-(U2-D50-Pad35)") (class "Default")
      (node (ref "U2") (pin "35") (pinfunction "D50_35") (pintype "unspecified"))
    )
    (net (code "227") (name "unconnected-(U2-D51-Pad36)") (class "Default")
      (node (ref "U2") (pin "36") (pinfunction "D51_36") (pintype "unspecified"))
    )
    (net (code "228") (name "unconnected-(U2-D52-Pad37)") (class "Default")
      (node (ref "U2") (pin "37") (pinfunction "D52_37") (pintype "unspecified"))
    )
    (net (code "229") (name "unconnected-(U2-D53-Pad38)") (class "Default")
      (node (ref "U2") (pin "38") (pinfunction "D53_38") (pintype "unspecified"))
    )
    (net (code "230") (name "unconnected-(U2-GND-Pad43)") (class "Default")
      (node (ref "U2") (pin "43") (pinfunction "GND_43") (pintype "unspecified"))
    )
    (net (code "231") (name "unconnected-(U2-GND-Pad83)") (class "Default")
      (node (ref "U2") (pin "83") (pinfunction "GND_83") (pintype "unspecified"))
    )
    (net (code "232") (name "unconnected-(U2-MISO-Pad40)") (class "Default")
      (node (ref "U2") (pin "40") (pinfunction "MISO_40") (pintype "unspecified"))
    )
    (net (code "233") (name "unconnected-(U2-MOSI-Pad41)") (class "Default")
      (node (ref "U2") (pin "41") (pinfunction "MOSI_41") (pintype "unspecified"))
    )
    (net (code "234") (name "unconnected-(U2-RST-Pad44)") (class "Default")
      (node (ref "U2") (pin "44") (pinfunction "RST_44") (pintype "unspecified"))
    )
    (net (code "235") (name "unconnected-(U2-RST-Pad78)") (class "Default")
      (node (ref "U2") (pin "78") (pinfunction "RST_78") (pintype "unspecified"))
    )
    (net (code "236") (name "unconnected-(U2-RX-Pad75)") (class "Default")
      (node (ref "U2") (pin "75") (pinfunction "RX_75") (pintype "unspecified"))
    )
    (net (code "237") (name "unconnected-(U2-SCK-Pad42)") (class "Default")
      (node (ref "U2") (pin "42") (pinfunction "SCK_42") (pintype "unspecified"))
    )
    (net (code "238") (name "unconnected-(U2-TX-Pad76)") (class "Default")
      (node (ref "U2") (pin "76") (pinfunction "TX_76") (pintype "unspecified"))
    )
    (net (code "239") (name "unconnected-(U2-VCC-Pad39)") (class "Default")
      (node (ref "U2") (pin "39") (pinfunction "VCC_39") (pintype "unspecified"))
    )
    (net (code "240") (name "unconnected-(U2-VIN-Pad85)") (class "Default")
      (node (ref "U2") (pin "85") (pinfunction "VIN_85") (pintype "unspecified"))
    )
  )
)
